# uart.net
KiCad netlist of a schematic drawn in EAGLE
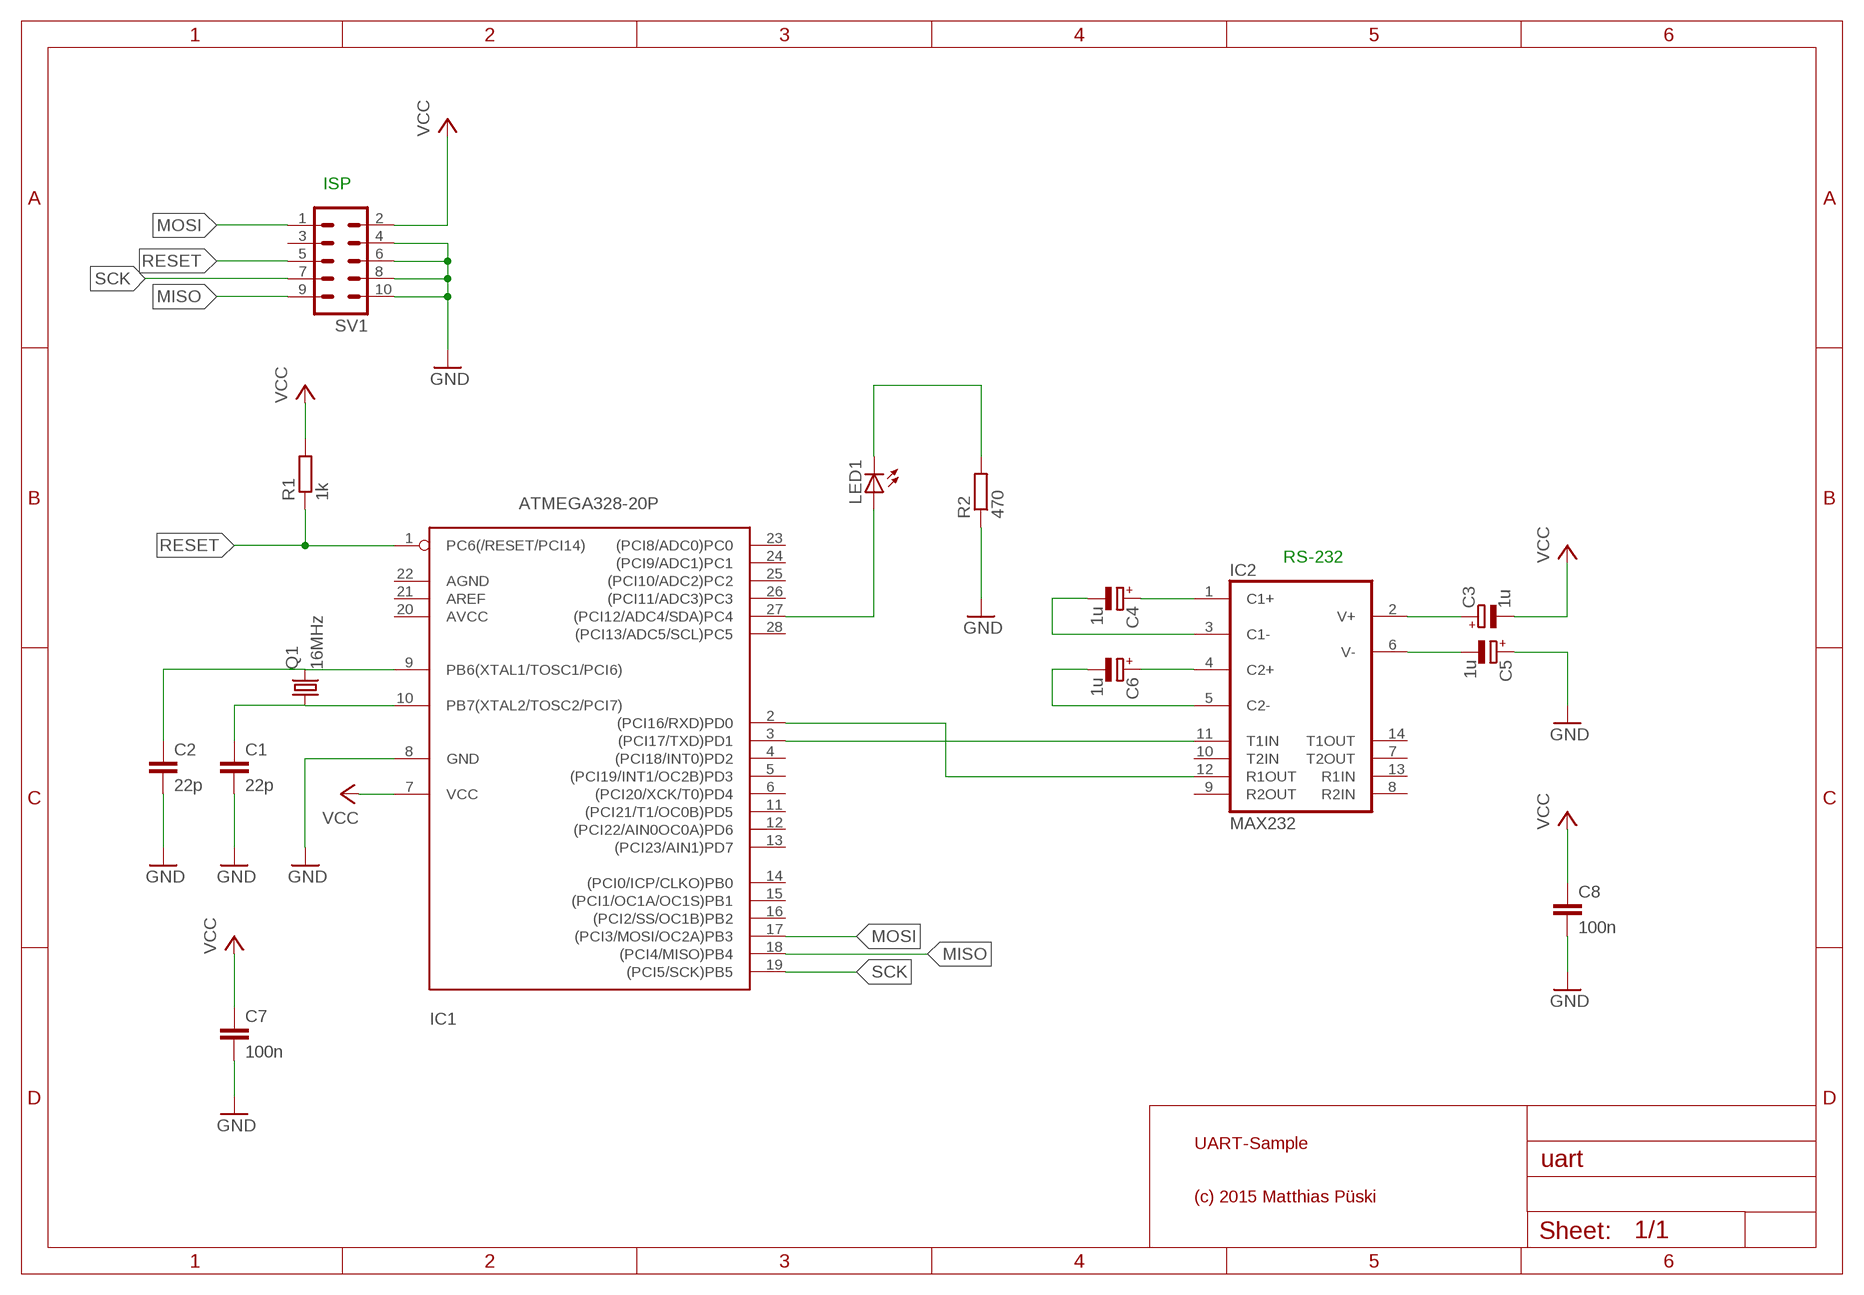
[diagram p0: schematic, sheet 1]

(export (version "E")
  (design (tool "Eeschema 10.0.6"))
  (components
    (comp (ref "C1")
      (value "22p")
      (footprint "eagle-import:C025-024X044")
      (libsource (lib "eagle-import") (part "C-EU025-024X044"))
    )
    (comp (ref "C2")
      (value "22p")
      (footprint "eagle-import:C025-024X044")
      (libsource (lib "eagle-import") (part "C-EU025-024X044"))
    )
    (comp (ref "C3")
      (value "1u")
      (footprint "eagle-import:E2,5-5")
      (libsource (lib "eagle-import") (part "CPOL-EUE2.5-5"))
    )
    (comp (ref "C4")
      (value "1u")
      (footprint "eagle-import:E2,5-5")
      (libsource (lib "eagle-import") (part "CPOL-EUE2.5-5"))
    )
    (comp (ref "C5")
      (value "1u")
      (footprint "eagle-import:E2,5-5")
      (libsource (lib "eagle-import") (part "CPOL-EUE2.5-5"))
    )
    (comp (ref "C6")
      (value "1u")
      (footprint "eagle-import:E2,5-5")
      (libsource (lib "eagle-import") (part "CPOL-EUE2.5-5"))
    )
    (comp (ref "C7")
      (value "100n")
      (footprint "eagle-import:C025-024X044")
      (libsource (lib "eagle-import") (part "C-EU025-024X044"))
    )
    (comp (ref "C8")
      (value "100n")
      (footprint "eagle-import:C025-024X044")
      (libsource (lib "eagle-import") (part "C-EU025-024X044"))
    )
    (comp (ref "IC1")
      (value "ATMEGA328-20P")
      (footprint "eagle-import:DIL28-3")
      (libsource (lib "eagle-import") (part "ATMEGA328P-20"))
    )
    (comp (ref "IC2")
      (value "MAX232")
      (footprint "eagle-import:DIL16")
      (fields (field (name "MF") "MAXIM") (field (name "MPN") "MAX232ACPE+"))
      (libsource (lib "eagle-import") (part "MAX232"))
    )
    (comp (ref "LED1")
      (value "LED5MM")
      (footprint "eagle-import:LED5MM")
      (libsource (lib "eagle-import") (part "LED5MM"))
    )
    (comp (ref "Q1")
      (value "16MHz")
      (footprint "eagle-import:HC49U-V")
      (libsource (lib "eagle-import") (part "CRYSTALHC49U-V"))
    )
    (comp (ref "R1")
      (value "1k")
      (footprint "eagle-import:0204_7")
      (libsource (lib "eagle-import") (part "R-EU_0204/7"))
    )
    (comp (ref "R2")
      (value "470")
      (footprint "eagle-import:0204_7")
      (libsource (lib "eagle-import") (part "R-EU_0204/7"))
    )
    (comp (ref "SV1")
      (value "ML10")
      (footprint "eagle-import:ML10")
      (libsource (lib "eagle-import") (part "ML10"))
    )
  )
  (nets
    (net (code "1") (name "GND") (class "Default")
      (node (ref "C1") (pin "2") (pinfunction "2_2") (pintype "passive"))
      (node (ref "C2") (pin "2") (pinfunction "2_2") (pintype "passive"))
      (node (ref "C5") (pin "+") (pinfunction "+_+") (pintype "passive"))
      (node (ref "C7") (pin "2") (pinfunction "2_2") (pintype "passive"))
      (node (ref "C8") (pin "2") (pinfunction "2_2") (pintype "passive"))
      (node (ref "IC1") (pin "8") (pinfunction "GND_8") (pintype "bidirectional"))
      (node (ref "R2") (pin "1") (pinfunction "1_1") (pintype "passive"))
      (node (ref "SV1") (pin "10") (pinfunction "10_10") (pintype "passive"))
      (node (ref "SV1") (pin "4") (pinfunction "4_4") (pintype "passive"))
      (node (ref "SV1") (pin "6") (pinfunction "6_6") (pintype "passive"))
      (node (ref "SV1") (pin "8") (pinfunction "8_8") (pintype "passive"))
    )
    (net (code "2") (name "MISO") (class "Default")
      (node (ref "IC1") (pin "18") (pinfunction "(PCI4/MISO)PB4_18") (pintype "bidirectional"))
      (node (ref "SV1") (pin "9") (pinfunction "9_9") (pintype "passive"))
    )
    (net (code "3") (name "MOSI") (class "Default")
      (node (ref "IC1") (pin "17") (pinfunction "(PCI3/MOSI/OC2A)PB3_17") (pintype "bidirectional"))
      (node (ref "SV1") (pin "1") (pinfunction "1_1") (pintype "passive"))
    )
    (net (code "4") (name "Net-(IC1-(PCI12{slash}ADC4{slash}SDA)PC4)") (class "Default")
      (node (ref "IC1") (pin "27") (pinfunction "(PCI12/ADC4/SDA)PC4_27") (pintype "bidirectional"))
      (node (ref "LED1") (pin "A") (pinfunction "A_A") (pintype "passive"))
    )
    (net (code "5") (name "Net-(IC1-(PCI16{slash}RXD)PD0)") (class "Default")
      (node (ref "IC1") (pin "2") (pinfunction "(PCI16/RXD)PD0_2") (pintype "bidirectional"))
      (node (ref "IC2") (pin "12") (pinfunction "R1OUT_12") (pintype "output"))
    )
    (net (code "6") (name "Net-(IC1-(PCI17{slash}TXD)PD1)") (class "Default")
      (node (ref "IC1") (pin "3") (pinfunction "(PCI17/TXD)PD1_3") (pintype "bidirectional"))
      (node (ref "IC2") (pin "11") (pinfunction "T1IN_11") (pintype "input"))
    )
    (net (code "7") (name "Net-(IC1-PB6(XTAL1{slash}TOSC1{slash}PCI6))") (class "Default")
      (node (ref "C2") (pin "1") (pinfunction "1_1") (pintype "passive"))
      (node (ref "IC1") (pin "9") (pinfunction "PB6(XTAL1/TOSC1/PCI6)_9") (pintype "bidirectional"))
      (node (ref "Q1") (pin "2") (pinfunction "2_2") (pintype "passive"))
    )
    (net (code "8") (name "Net-(IC1-PB7(XTAL2{slash}TOSC2{slash}PCI7))") (class "Default")
      (node (ref "C1") (pin "1") (pinfunction "1_1") (pintype "passive"))
      (node (ref "IC1") (pin "10") (pinfunction "PB7(XTAL2/TOSC2/PCI7)_10") (pintype "bidirectional"))
      (node (ref "Q1") (pin "1") (pinfunction "1_1") (pintype "passive"))
    )
    (net (code "9") (name "Net-(IC2A-C1+)") (class "Default")
      (node (ref "C4") (pin "+") (pinfunction "+_+") (pintype "passive"))
      (node (ref "IC2") (pin "1") (pinfunction "C1+_1") (pintype "bidirectional"))
    )
    (net (code "10") (name "Net-(IC2A-C1-)") (class "Default")
      (node (ref "C4") (pin "-") (pinfunction "-_-") (pintype "passive"))
      (node (ref "IC2") (pin "3") (pinfunction "C1-_3") (pintype "bidirectional"))
    )
    (net (code "11") (name "Net-(IC2A-C2+)") (class "Default")
      (node (ref "C6") (pin "+") (pinfunction "+_+") (pintype "passive"))
      (node (ref "IC2") (pin "4") (pinfunction "C2+_4") (pintype "bidirectional"))
    )
    (net (code "12") (name "Net-(IC2A-C2-)") (class "Default")
      (node (ref "C6") (pin "-") (pinfunction "-_-") (pintype "passive"))
      (node (ref "IC2") (pin "5") (pinfunction "C2-_5") (pintype "bidirectional"))
    )
    (net (code "13") (name "Net-(IC2A-V+)") (class "Default")
      (node (ref "C3") (pin "+") (pinfunction "+_+") (pintype "passive"))
      (node (ref "IC2") (pin "2") (pinfunction "V+_2") (pintype "bidirectional"))
    )
    (net (code "14") (name "Net-(IC2A-V-)") (class "Default")
      (node (ref "C5") (pin "-") (pinfunction "-_-") (pintype "passive"))
      (node (ref "IC2") (pin "6") (pinfunction "V-_6") (pintype "bidirectional"))
    )
    (net (code "15") (name "Net-(LED1-C)") (class "Default")
      (node (ref "LED1") (pin "K") (pinfunction "C_K") (pintype "passive"))
      (node (ref "R2") (pin "2") (pinfunction "2_2") (pintype "passive"))
    )
    (net (code "16") (name "RESET") (class "Default")
      (node (ref "IC1") (pin "1") (pinfunction "PC6(/RESET/PCI14)_1") (pintype "bidirectional"))
      (node (ref "R1") (pin "1") (pinfunction "1_1") (pintype "passive"))
      (node (ref "SV1") (pin "5") (pinfunction "5_5") (pintype "passive"))
    )
    (net (code "17") (name "SCK") (class "Default")
      (node (ref "IC1") (pin "19") (pinfunction "(PCI5/SCK)PB5_19") (pintype "bidirectional"))
      (node (ref "SV1") (pin "7") (pinfunction "7_7") (pintype "passive"))
    )
    (net (code "18") (name "VCC") (class "Default")
      (node (ref "C3") (pin "-") (pinfunction "-_-") (pintype "passive"))
      (node (ref "C7") (pin "1") (pinfunction "1_1") (pintype "passive"))
      (node (ref "C8") (pin "1") (pinfunction "1_1") (pintype "passive"))
      (node (ref "IC1") (pin "7") (pinfunction "VCC_7") (pintype "bidirectional"))
      (node (ref "R1") (pin "2") (pinfunction "2_2") (pintype "passive"))
      (node (ref "SV1") (pin "2") (pinfunction "2_2") (pintype "passive"))
    )
    (net (code "19") (name "unconnected-(IC1-(PCI0{slash}ICP{slash}CLKO)PB0-Pad14)") (class "Default")
      (node (ref "IC1") (pin "14") (pinfunction "(PCI0/ICP/CLKO)PB0_14") (pintype "bidirectional"))
    )
    (net (code "20") (name "unconnected-(IC1-(PCI1{slash}OC1A{slash}OC1S)PB1-Pad15)") (class "Default")
      (node (ref "IC1") (pin "15") (pinfunction "(PCI1/OC1A/OC1S)PB1_15") (pintype "bidirectional"))
    )
    (net (code "21") (name "unconnected-(IC1-(PCI2{slash}SS{slash}OC1B)PB2-Pad16)") (class "Default")
      (node (ref "IC1") (pin "16") (pinfunction "(PCI2/SS/OC1B)PB2_16") (pintype "bidirectional"))
    )
    (net (code "22") (name "unconnected-(IC1-(PCI8{slash}ADC0)PC0-Pad23)") (class "Default")
      (node (ref "IC1") (pin "23") (pinfunction "(PCI8/ADC0)PC0_23") (pintype "bidirectional"))
    )
    (net (code "23") (name "unconnected-(IC1-(PCI9{slash}ADC1)PC1-Pad24)") (class "Default")
      (node (ref "IC1") (pin "24") (pinfunction "(PCI9/ADC1)PC1_24") (pintype "bidirectional"))
    )
    (net (code "24") (name "unconnected-(IC1-(PCI10{slash}ADC2)PC2-Pad25)") (class "Default")
      (node (ref "IC1") (pin "25") (pinfunction "(PCI10/ADC2)PC2_25") (pintype "bidirectional"))
    )
    (net (code "25") (name "unconnected-(IC1-(PCI11{slash}ADC3)PC3-Pad26)") (class "Default")
      (node (ref "IC1") (pin "26") (pinfunction "(PCI11/ADC3)PC3_26") (pintype "bidirectional"))
    )
    (net (code "26") (name "unconnected-(IC1-(PCI13{slash}ADC5{slash}SCL)PC5-Pad28)") (class "Default")
      (node (ref "IC1") (pin "28") (pinfunction "(PCI13/ADC5/SCL)PC5_28") (pintype "bidirectional"))
    )
    (net (code "27") (name "unconnected-(IC1-(PCI18{slash}INT0)PD2-Pad4)") (class "Default")
      (node (ref "IC1") (pin "4") (pinfunction "(PCI18/INT0)PD2_4") (pintype "bidirectional"))
    )
    (net (code "28") (name "unconnected-(IC1-(PCI19{slash}INT1{slash}OC2B)PD3-Pad5)") (class "Default")
      (node (ref "IC1") (pin "5") (pinfunction "(PCI19/INT1/OC2B)PD3_5") (pintype "bidirectional"))
    )
    (net (code "29") (name "unconnected-(IC1-(PCI20{slash}XCK{slash}T0)PD4-Pad6)") (class "Default")
      (node (ref "IC1") (pin "6") (pinfunction "(PCI20/XCK/T0)PD4_6") (pintype "bidirectional"))
    )
    (net (code "30") (name "unconnected-(IC1-(PCI21{slash}T1{slash}OC0B)PD5-Pad11)") (class "Default")
      (node (ref "IC1") (pin "11") (pinfunction "(PCI21/T1/OC0B)PD5_11") (pintype "bidirectional"))
    )
    (net (code "31") (name "unconnected-(IC1-(PCI22{slash}AIN0OC0A)PD6-Pad12)") (class "Default")
      (node (ref "IC1") (pin "12") (pinfunction "(PCI22/AIN0OC0A)PD6_12") (pintype "bidirectional"))
    )
    (net (code "32") (name "unconnected-(IC1-(PCI23{slash}AIN1)PD7-Pad13)") (class "Default")
      (node (ref "IC1") (pin "13") (pinfunction "(PCI23/AIN1)PD7_13") (pintype "bidirectional"))
    )
    (net (code "33") (name "unconnected-(IC1-AGND-Pad22)") (class "Default")
      (node (ref "IC1") (pin "22") (pinfunction "AGND_22") (pintype "bidirectional"))
    )
    (net (code "34") (name "unconnected-(IC1-AREF-Pad21)") (class "Default")
      (node (ref "IC1") (pin "21") (pinfunction "AREF_21") (pintype "bidirectional"))
    )
    (net (code "35") (name "unconnected-(IC1-AVCC-Pad20)") (class "Default")
      (node (ref "IC1") (pin "20") (pinfunction "AVCC_20") (pintype "bidirectional"))
    )
    (net (code "36") (name "unconnected-(IC2A-R1IN-Pad13)") (class "Default")
      (node (ref "IC2") (pin "13") (pinfunction "R1IN_13") (pintype "input"))
    )
    (net (code "37") (name "unconnected-(IC2A-R2IN-Pad8)") (class "Default")
      (node (ref "IC2") (pin "8") (pinfunction "R2IN_8") (pintype "input"))
    )
    (net (code "38") (name "unconnected-(IC2A-R2OUT-Pad9)") (class "Default")
      (node (ref "IC2") (pin "9") (pinfunction "R2OUT_9") (pintype "output"))
    )
    (net (code "39") (name "unconnected-(IC2A-T1OUT-Pad14)") (class "Default")
      (node (ref "IC2") (pin "14") (pinfunction "T1OUT_14") (pintype "output"))
    )
    (net (code "40") (name "unconnected-(IC2A-T2IN-Pad10)") (class "Default")
      (node (ref "IC2") (pin "10") (pinfunction "T2IN_10") (pintype "input"))
    )
    (net (code "41") (name "unconnected-(IC2A-T2OUT-Pad7)") (class "Default")
      (node (ref "IC2") (pin "7") (pinfunction "T2OUT_7") (pintype "output"))
    )
    (net (code "42") (name "unconnected-(SV1-Pad3)") (class "Default")
      (node (ref "SV1") (pin "3") (pinfunction "3_3") (pintype "passive"))
    )
  )
)
